# ir-sensor-breakout-mk-2_0.net
KiCad netlist of a schematic drawn in EAGLE
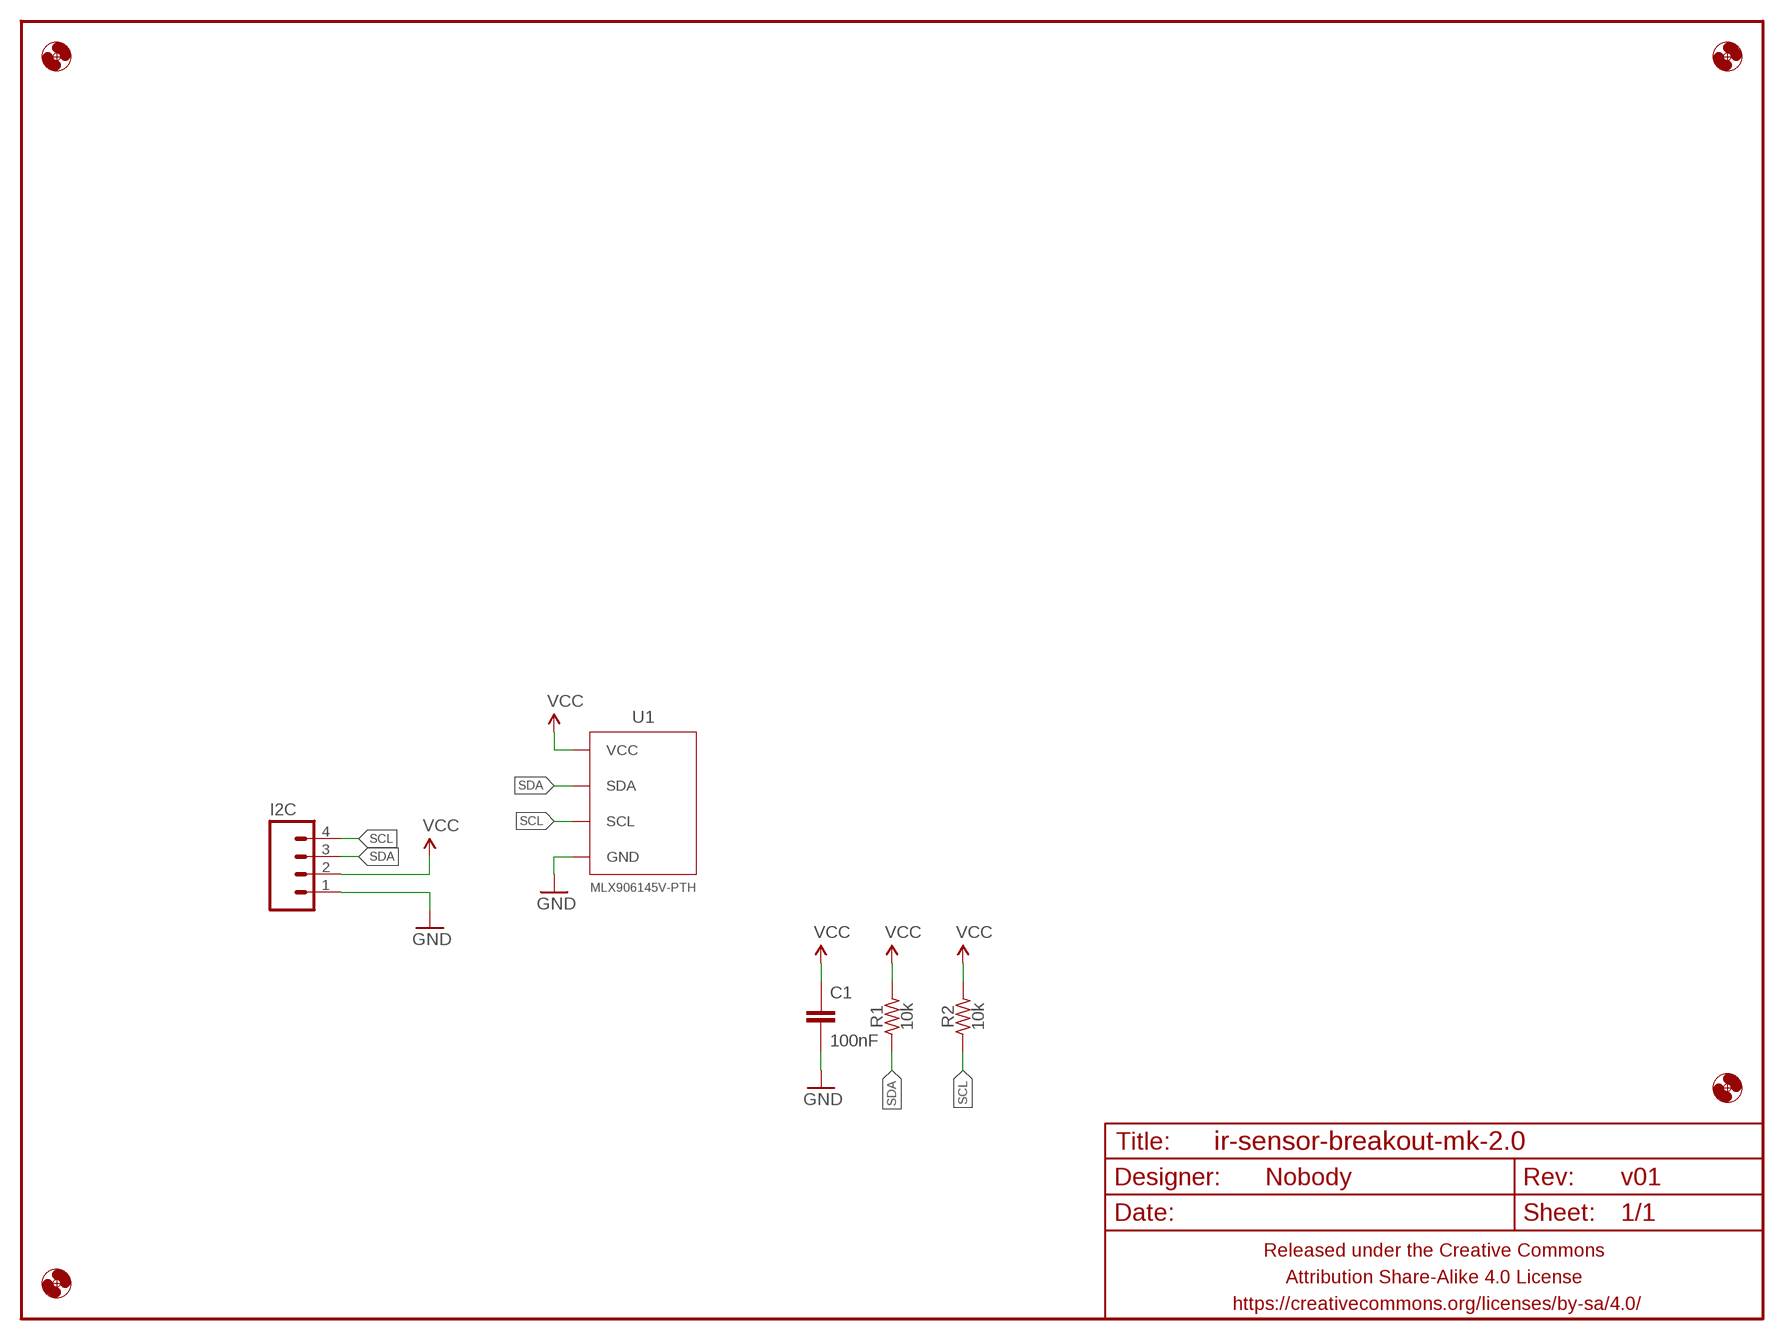
[diagram p0: schematic, sheet 1]

(export (version "E")
  (design (tool "Eeschema 10.0.6"))
  (components
    (comp (ref "C1")
      (value "100nF")
      (footprint "eagle-import:C025-024X044")
      (libsource (lib "eagle-import") (part "CAPACITOR-CERAMIC025-024X044"))
    )
    (comp (ref "FRAME1")
      (value "FRAME-LETTERNO_PACKAGE")
      (footprint "eagle-import:DUMMY")
      (fields (field (name "DESIGNER") "Nobody"))
      (libsource (lib "eagle-import") (part "FRAME-LETTERNO_PACKAGE"))
    )
    (comp (ref "H1")
      (value "HOLE#2")
      (footprint "eagle-import:HOLE-#2")
      (libsource (lib "eagle-import") (part "HOLE#2"))
    )
    (comp (ref "H2")
      (value "HOLE#2")
      (footprint "eagle-import:HOLE-#2")
      (libsource (lib "eagle-import") (part "HOLE#2"))
    )
    (comp (ref "H3")
      (value "HOLE#2")
      (footprint "eagle-import:HOLE-#2")
      (libsource (lib "eagle-import") (part "HOLE#2"))
    )
    (comp (ref "H4")
      (value "HOLE#2")
      (footprint "eagle-import:HOLE-#2")
      (libsource (lib "eagle-import") (part "HOLE#2"))
    )
    (comp (ref "I2C")
      (value "M04JST-PTH-VERT")
      (footprint "eagle-import:JST-4-PH-VERT-PTH")
      (libsource (lib "eagle-import") (part "M04JST-PTH-VERT"))
    )
    (comp (ref "R1")
      (value "10k")
      (footprint "eagle-import:RESISTOR-AXIAL-PTH-5.08MM")
      (libsource (lib "eagle-import") (part "RESISTORPTH-AXIAL-5.08MM"))
    )
    (comp (ref "R2")
      (value "10k")
      (footprint "eagle-import:RESISTOR-AXIAL-PTH-5.08MM")
      (libsource (lib "eagle-import") (part "RESISTORPTH-AXIAL-5.08MM"))
    )
    (comp (ref "U1")
      (value "MLX906145V-PTH")
      (footprint "eagle-import:TO-39-4")
      (libsource (lib "eagle-import") (part "MLX906145V-PTH"))
    )
  )
  (nets
    (net (code "1") (name "GND") (class "Default")
      (node (ref "C1") (pin "2") (pinfunction "2_2") (pintype "passive"))
      (node (ref "I2C") (pin "1") (pinfunction "1_1") (pintype "passive"))
      (node (ref "U1") (pin "4") (pinfunction "GND_4") (pintype "bidirectional"))
    )
    (net (code "2") (name "SCL") (class "Default")
      (node (ref "I2C") (pin "4") (pinfunction "4_4") (pintype "passive"))
      (node (ref "R2") (pin "P$1") (pinfunction "1_P$1") (pintype "passive"))
      (node (ref "U1") (pin "1") (pinfunction "SCL_1") (pintype "bidirectional"))
    )
    (net (code "3") (name "SDA") (class "Default")
      (node (ref "I2C") (pin "3") (pinfunction "3_3") (pintype "passive"))
      (node (ref "R1") (pin "P$1") (pinfunction "1_P$1") (pintype "passive"))
      (node (ref "U1") (pin "2") (pinfunction "SDA_2") (pintype "bidirectional"))
    )
    (net (code "4") (name "VCC") (class "Default")
      (node (ref "C1") (pin "1") (pinfunction "1_1") (pintype "passive"))
      (node (ref "I2C") (pin "2") (pinfunction "2_2") (pintype "passive"))
      (node (ref "R1") (pin "P$2") (pinfunction "2_P$2") (pintype "passive"))
      (node (ref "R2") (pin "P$2") (pinfunction "2_P$2") (pintype "passive"))
      (node (ref "U1") (pin "3") (pinfunction "VCC_3") (pintype "bidirectional"))
    )
  )
)
